# CBB-Proto-r01.net
KiCad netlist of a schematic drawn in EAGLE
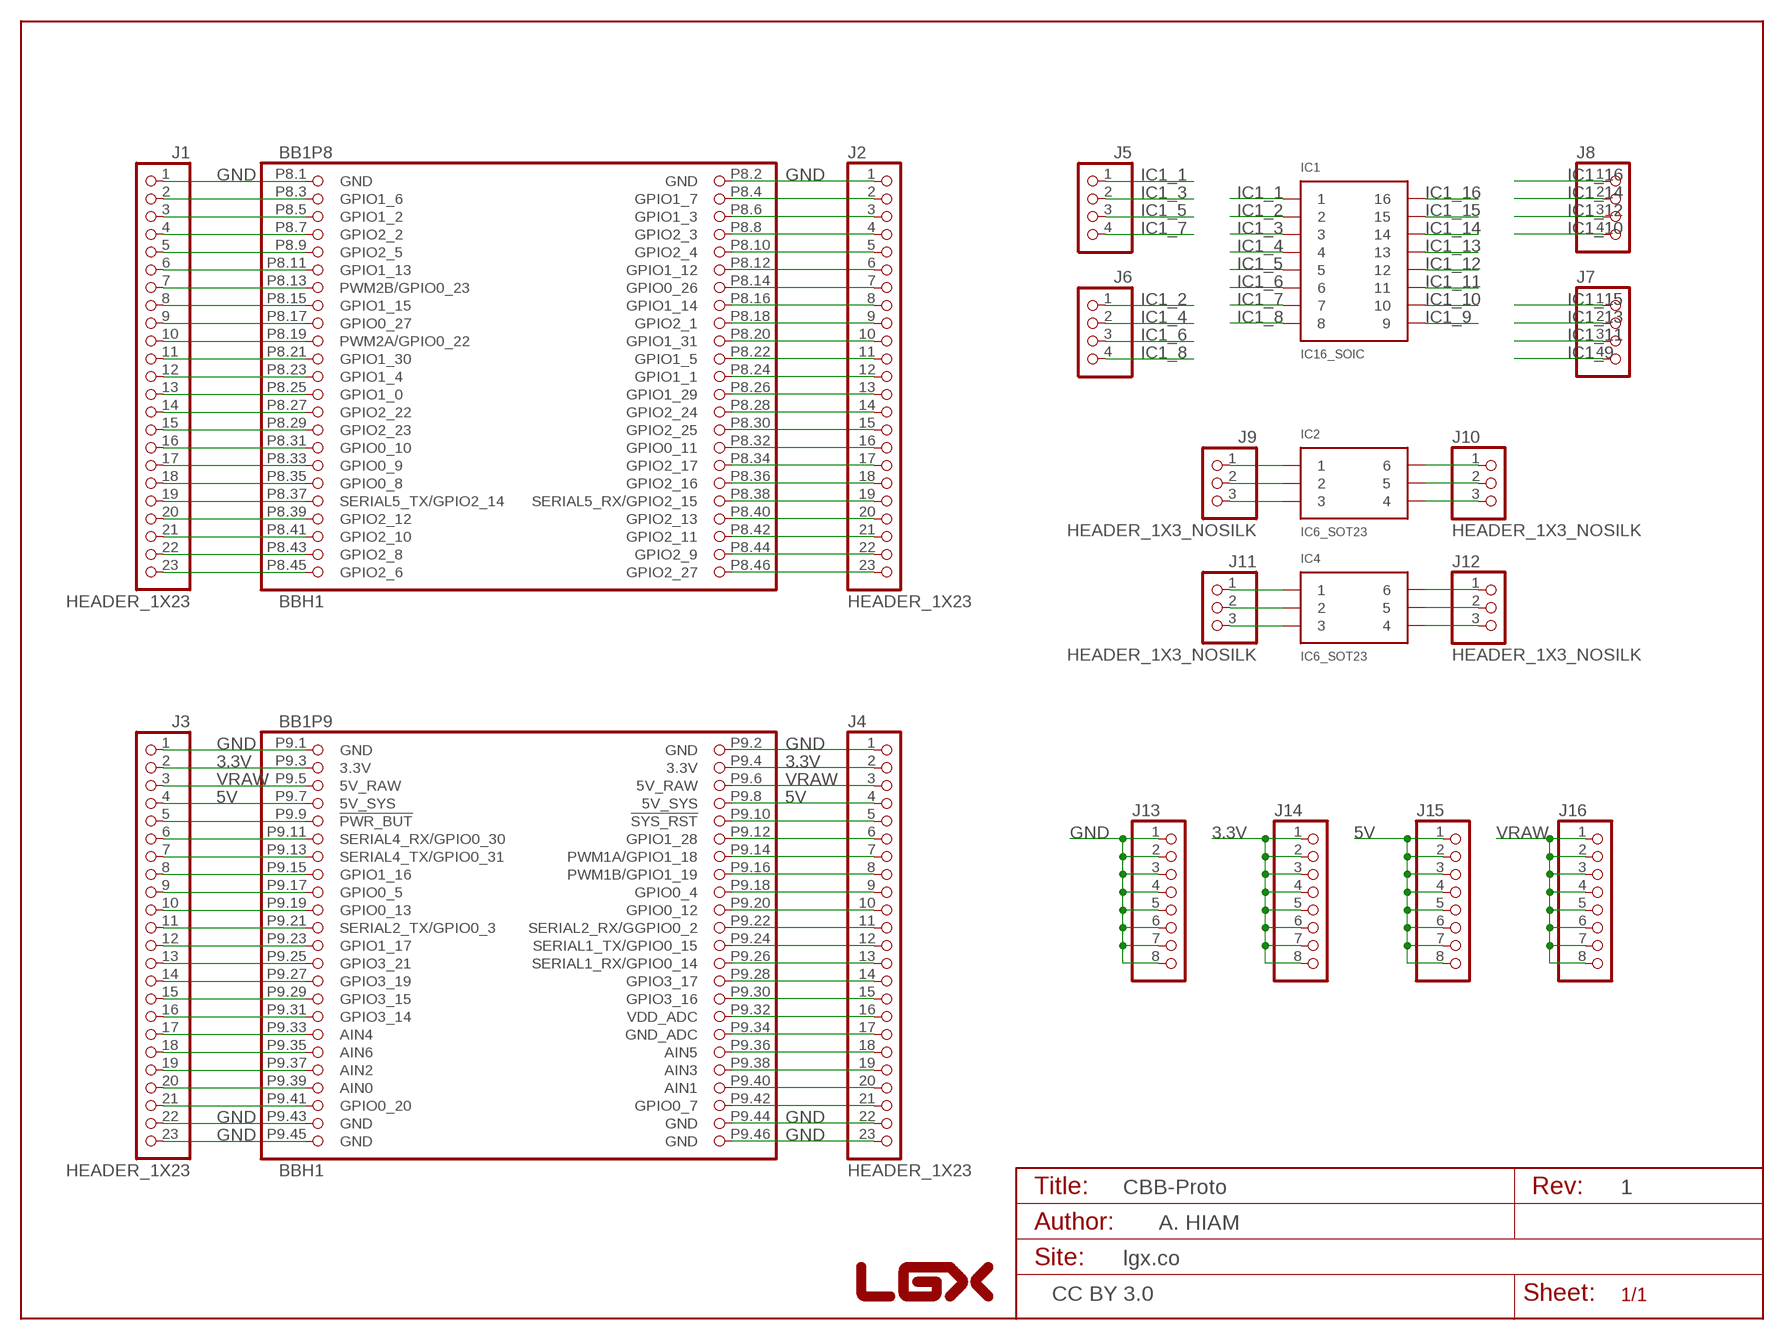
[diagram p0: schematic, sheet 1]

(export (version "E")
  (design (tool "Eeschema 10.0.6"))
  (components
    (comp (ref "BB1")
      (value "BBH1")
      (footprint "eagle-import:BB_CAPE")
      (libsource (lib "eagle-import") (part "BBH1"))
    )
    (comp (ref "IC1")
      (value "IC16_SOIC")
      (footprint "eagle-import:SOIC16")
      (libsource (lib "eagle-import") (part "IC16_SOIC"))
    )
    (comp (ref "IC2")
      (value "IC6_SOT23")
      (footprint "eagle-import:SOT23-6")
      (libsource (lib "eagle-import") (part "IC6_SOT23"))
    )
    (comp (ref "IC4")
      (value "IC6_SOT23")
      (footprint "eagle-import:SOT23-6")
      (libsource (lib "eagle-import") (part "IC6_SOT23"))
    )
    (comp (ref "J1")
      (value "HEADER_1X23")
      (footprint "eagle-import:HEADER_1X23")
      (libsource (lib "eagle-import") (part "HEADER_1X23"))
    )
    (comp (ref "J2")
      (value "HEADER_1X23")
      (footprint "eagle-import:HEADER_1X23")
      (libsource (lib "eagle-import") (part "HEADER_1X23"))
    )
    (comp (ref "J3")
      (value "HEADER_1X23")
      (footprint "eagle-import:HEADER_1X23")
      (libsource (lib "eagle-import") (part "HEADER_1X23"))
    )
    (comp (ref "J4")
      (value "HEADER_1X23")
      (footprint "eagle-import:HEADER_1X23")
      (libsource (lib "eagle-import") (part "HEADER_1X23"))
    )
    (comp (ref "J5")
      (value "HEADER_1X4")
      (footprint "eagle-import:HEADER_1X4")
      (libsource (lib "eagle-import") (part "HEADER_1X4"))
    )
    (comp (ref "J6")
      (value "HEADER_1X4")
      (footprint "eagle-import:HEADER_1X4")
      (libsource (lib "eagle-import") (part "HEADER_1X4"))
    )
    (comp (ref "J7")
      (value "HEADER_1X4")
      (footprint "eagle-import:HEADER_1X4")
      (libsource (lib "eagle-import") (part "HEADER_1X4"))
    )
    (comp (ref "J8")
      (value "HEADER_1X4")
      (footprint "eagle-import:HEADER_1X4")
      (libsource (lib "eagle-import") (part "HEADER_1X4"))
    )
    (comp (ref "J9")
      (value "HEADER_1X3_NOSILK")
      (footprint "eagle-import:HEADER_1X3_NOSILK")
      (libsource (lib "eagle-import") (part "HEADER_1X3_NOSILK"))
    )
    (comp (ref "J10")
      (value "HEADER_1X3_NOSILK")
      (footprint "eagle-import:HEADER_1X3_NOSILK")
      (libsource (lib "eagle-import") (part "HEADER_1X3_NOSILK"))
    )
    (comp (ref "J11")
      (value "HEADER_1X3_NOSILK")
      (footprint "eagle-import:HEADER_1X3_NOSILK")
      (libsource (lib "eagle-import") (part "HEADER_1X3_NOSILK"))
    )
    (comp (ref "J12")
      (value "HEADER_1X3_NOSILK")
      (footprint "eagle-import:HEADER_1X3_NOSILK")
      (libsource (lib "eagle-import") (part "HEADER_1X3_NOSILK"))
    )
    (comp (ref "J13")
      (value "HEADER_1X8")
      (footprint "eagle-import:HEADER_1X8")
      (libsource (lib "eagle-import") (part "HEADER_1X8"))
    )
    (comp (ref "J14")
      (value "HEADER_1X8")
      (footprint "eagle-import:HEADER_1X8")
      (libsource (lib "eagle-import") (part "HEADER_1X8"))
    )
    (comp (ref "J15")
      (value "HEADER_1X8")
      (footprint "eagle-import:HEADER_1X8")
      (libsource (lib "eagle-import") (part "HEADER_1X8"))
    )
    (comp (ref "J16")
      (value "HEADER_1X8")
      (footprint "eagle-import:HEADER_1X8")
      (libsource (lib "eagle-import") (part "HEADER_1X8"))
    )
    (comp (ref "U$1")
      (value "LOGO-LGX")
      (footprint "eagle-import:LOGO-LGX")
      (libsource (lib "eagle-import") (part "LOGO-LGX"))
    )
  )
  (nets
    (net (code "1") (name "/3.3V") (class "Default")
      (node (ref "BB1") (pin "P9.3") (pinfunction "3.3V_P9.3") (pintype "power_in"))
      (node (ref "BB1") (pin "P9.4") (pinfunction "3.3V_P9.4") (pintype "power_in"))
      (node (ref "J14") (pin "1") (pinfunction "1_1") (pintype "passive"))
      (node (ref "J14") (pin "2") (pinfunction "2_2") (pintype "passive"))
      (node (ref "J14") (pin "3") (pinfunction "3_3") (pintype "passive"))
      (node (ref "J14") (pin "4") (pinfunction "4_4") (pintype "passive"))
      (node (ref "J14") (pin "5") (pinfunction "5_5") (pintype "passive"))
      (node (ref "J14") (pin "6") (pinfunction "6_6") (pintype "passive"))
      (node (ref "J14") (pin "7") (pinfunction "7_7") (pintype "passive"))
      (node (ref "J14") (pin "8") (pinfunction "8_8") (pintype "passive"))
      (node (ref "J3") (pin "2") (pinfunction "2_2") (pintype "passive"))
      (node (ref "J4") (pin "2") (pinfunction "2_2") (pintype "passive"))
    )
    (net (code "2") (name "/5V") (class "Default")
      (node (ref "BB1") (pin "P9.7") (pinfunction "5V_SYS_P9.7") (pintype "power_in"))
      (node (ref "BB1") (pin "P9.8") (pinfunction "5V_SYS_P9.8") (pintype "power_in"))
      (node (ref "J15") (pin "1") (pinfunction "1_1") (pintype "passive"))
      (node (ref "J15") (pin "2") (pinfunction "2_2") (pintype "passive"))
      (node (ref "J15") (pin "3") (pinfunction "3_3") (pintype "passive"))
      (node (ref "J15") (pin "4") (pinfunction "4_4") (pintype "passive"))
      (node (ref "J15") (pin "5") (pinfunction "5_5") (pintype "passive"))
      (node (ref "J15") (pin "6") (pinfunction "6_6") (pintype "passive"))
      (node (ref "J15") (pin "7") (pinfunction "7_7") (pintype "passive"))
      (node (ref "J15") (pin "8") (pinfunction "8_8") (pintype "passive"))
      (node (ref "J3") (pin "4") (pinfunction "4_4") (pintype "passive"))
      (node (ref "J4") (pin "4") (pinfunction "4_4") (pintype "passive"))
    )
    (net (code "3") (name "/GND") (class "Default")
      (node (ref "BB1") (pin "P8.1") (pinfunction "GND_P8.1") (pintype "power_in"))
      (node (ref "BB1") (pin "P8.2") (pinfunction "GND_P8.2") (pintype "power_in"))
      (node (ref "BB1") (pin "P9.1") (pinfunction "GND_P9.1") (pintype "power_in"))
      (node (ref "BB1") (pin "P9.2") (pinfunction "GND_P9.2") (pintype "power_in"))
      (node (ref "BB1") (pin "P9.43") (pinfunction "GND_P9.43") (pintype "bidirectional"))
      (node (ref "BB1") (pin "P9.44") (pinfunction "GND_P9.44") (pintype "bidirectional"))
      (node (ref "BB1") (pin "P9.45") (pinfunction "GND_P9.45") (pintype "bidirectional"))
      (node (ref "BB1") (pin "P9.46") (pinfunction "GND_P9.46") (pintype "bidirectional"))
      (node (ref "J1") (pin "1") (pinfunction "1_1") (pintype "passive"))
      (node (ref "J13") (pin "1") (pinfunction "1_1") (pintype "passive"))
      (node (ref "J13") (pin "2") (pinfunction "2_2") (pintype "passive"))
      (node (ref "J13") (pin "3") (pinfunction "3_3") (pintype "passive"))
      (node (ref "J13") (pin "4") (pinfunction "4_4") (pintype "passive"))
      (node (ref "J13") (pin "5") (pinfunction "5_5") (pintype "passive"))
      (node (ref "J13") (pin "6") (pinfunction "6_6") (pintype "passive"))
      (node (ref "J13") (pin "7") (pinfunction "7_7") (pintype "passive"))
      (node (ref "J13") (pin "8") (pinfunction "8_8") (pintype "passive"))
      (node (ref "J2") (pin "1") (pinfunction "1_1") (pintype "passive"))
      (node (ref "J3") (pin "1") (pinfunction "1_1") (pintype "passive"))
      (node (ref "J3") (pin "22") (pinfunction "22_22") (pintype "passive"))
      (node (ref "J3") (pin "23") (pinfunction "23_23") (pintype "passive"))
      (node (ref "J4") (pin "1") (pinfunction "1_1") (pintype "passive"))
      (node (ref "J4") (pin "22") (pinfunction "22_22") (pintype "passive"))
      (node (ref "J4") (pin "23") (pinfunction "23_23") (pintype "passive"))
    )
    (net (code "4") (name "/IC1_1") (class "Default")
      (node (ref "IC1") (pin "1") (pinfunction "1_1") (pintype "bidirectional"))
      (node (ref "J5") (pin "1") (pinfunction "1_1") (pintype "passive"))
    )
    (net (code "5") (name "/IC1_2") (class "Default")
      (node (ref "IC1") (pin "2") (pinfunction "2_2") (pintype "bidirectional"))
      (node (ref "J6") (pin "1") (pinfunction "1_1") (pintype "passive"))
    )
    (net (code "6") (name "/IC1_3") (class "Default")
      (node (ref "IC1") (pin "3") (pinfunction "3_3") (pintype "bidirectional"))
      (node (ref "J5") (pin "2") (pinfunction "2_2") (pintype "passive"))
    )
    (net (code "7") (name "/IC1_4") (class "Default")
      (node (ref "IC1") (pin "4") (pinfunction "4_4") (pintype "bidirectional"))
      (node (ref "J6") (pin "2") (pinfunction "2_2") (pintype "passive"))
    )
    (net (code "8") (name "/IC1_5") (class "Default")
      (node (ref "IC1") (pin "5") (pinfunction "5_5") (pintype "bidirectional"))
      (node (ref "J5") (pin "3") (pinfunction "3_3") (pintype "passive"))
    )
    (net (code "9") (name "/IC1_6") (class "Default")
      (node (ref "IC1") (pin "6") (pinfunction "6_6") (pintype "bidirectional"))
      (node (ref "J6") (pin "3") (pinfunction "3_3") (pintype "passive"))
    )
    (net (code "10") (name "/IC1_7") (class "Default")
      (node (ref "IC1") (pin "7") (pinfunction "7_7") (pintype "bidirectional"))
      (node (ref "J5") (pin "4") (pinfunction "4_4") (pintype "passive"))
    )
    (net (code "11") (name "/IC1_8") (class "Default")
      (node (ref "IC1") (pin "8") (pinfunction "8_8") (pintype "bidirectional"))
      (node (ref "J6") (pin "4") (pinfunction "4_4") (pintype "passive"))
    )
    (net (code "12") (name "/IC1_9") (class "Default")
      (node (ref "IC1") (pin "9") (pinfunction "9_9") (pintype "bidirectional"))
      (node (ref "J7") (pin "4") (pinfunction "4_4") (pintype "passive"))
    )
    (net (code "13") (name "/IC1_10") (class "Default")
      (node (ref "IC1") (pin "10") (pinfunction "10_10") (pintype "bidirectional"))
      (node (ref "J8") (pin "4") (pinfunction "4_4") (pintype "passive"))
    )
    (net (code "14") (name "/IC1_11") (class "Default")
      (node (ref "IC1") (pin "11") (pinfunction "11_11") (pintype "bidirectional"))
      (node (ref "J7") (pin "3") (pinfunction "3_3") (pintype "passive"))
    )
    (net (code "15") (name "/IC1_12") (class "Default")
      (node (ref "IC1") (pin "12") (pinfunction "12_12") (pintype "bidirectional"))
      (node (ref "J8") (pin "3") (pinfunction "3_3") (pintype "passive"))
    )
    (net (code "16") (name "/IC1_13") (class "Default")
      (node (ref "IC1") (pin "13") (pinfunction "13_13") (pintype "bidirectional"))
      (node (ref "J7") (pin "2") (pinfunction "2_2") (pintype "passive"))
    )
    (net (code "17") (name "/IC1_14") (class "Default")
      (node (ref "IC1") (pin "14") (pinfunction "14_14") (pintype "bidirectional"))
      (node (ref "J8") (pin "2") (pinfunction "2_2") (pintype "passive"))
    )
    (net (code "18") (name "/IC1_15") (class "Default")
      (node (ref "IC1") (pin "15") (pinfunction "15_15") (pintype "bidirectional"))
      (node (ref "J7") (pin "1") (pinfunction "1_1") (pintype "passive"))
    )
    (net (code "19") (name "/IC1_16") (class "Default")
      (node (ref "IC1") (pin "16") (pinfunction "16_16") (pintype "bidirectional"))
      (node (ref "J8") (pin "1") (pinfunction "1_1") (pintype "passive"))
    )
    (net (code "20") (name "/VRAW") (class "Default")
      (node (ref "BB1") (pin "P9.5") (pinfunction "5V_RAW_P9.5") (pintype "power_in"))
      (node (ref "BB1") (pin "P9.6") (pinfunction "5V_RAW_P9.6") (pintype "power_in"))
      (node (ref "J16") (pin "1") (pinfunction "1_1") (pintype "passive"))
      (node (ref "J16") (pin "2") (pinfunction "2_2") (pintype "passive"))
      (node (ref "J16") (pin "3") (pinfunction "3_3") (pintype "passive"))
      (node (ref "J16") (pin "4") (pinfunction "4_4") (pintype "passive"))
      (node (ref "J16") (pin "5") (pinfunction "5_5") (pintype "passive"))
      (node (ref "J16") (pin "6") (pinfunction "6_6") (pintype "passive"))
      (node (ref "J16") (pin "7") (pinfunction "7_7") (pintype "passive"))
      (node (ref "J16") (pin "8") (pinfunction "8_8") (pintype "passive"))
      (node (ref "J3") (pin "3") (pinfunction "3_3") (pintype "passive"))
      (node (ref "J4") (pin "3") (pinfunction "3_3") (pintype "passive"))
    )
    (net (code "21") (name "Net-(BB1A-GPIO0_8)") (class "Default")
      (node (ref "BB1") (pin "P8.35") (pinfunction "GPIO0_8_P8.35") (pintype "bidirectional"))
      (node (ref "J1") (pin "18") (pinfunction "18_18") (pintype "passive"))
    )
    (net (code "22") (name "Net-(BB1A-GPIO0_9)") (class "Default")
      (node (ref "BB1") (pin "P8.33") (pinfunction "GPIO0_9_P8.33") (pintype "bidirectional"))
      (node (ref "J1") (pin "17") (pinfunction "17_17") (pintype "passive"))
    )
    (net (code "23") (name "Net-(BB1A-GPIO0_10)") (class "Default")
      (node (ref "BB1") (pin "P8.31") (pinfunction "GPIO0_10_P8.31") (pintype "bidirectional"))
      (node (ref "J1") (pin "16") (pinfunction "16_16") (pintype "passive"))
    )
    (net (code "24") (name "Net-(BB1A-GPIO0_11)") (class "Default")
      (node (ref "BB1") (pin "P8.32") (pinfunction "GPIO0_11_P8.32") (pintype "bidirectional"))
      (node (ref "J2") (pin "16") (pinfunction "16_16") (pintype "passive"))
    )
    (net (code "25") (name "Net-(BB1A-GPIO0_26)") (class "Default")
      (node (ref "BB1") (pin "P8.14") (pinfunction "GPIO0_26_P8.14") (pintype "bidirectional"))
      (node (ref "J2") (pin "7") (pinfunction "7_7") (pintype "passive"))
    )
    (net (code "26") (name "Net-(BB1A-GPIO0_27)") (class "Default")
      (node (ref "BB1") (pin "P8.17") (pinfunction "GPIO0_27_P8.17") (pintype "bidirectional"))
      (node (ref "J1") (pin "9") (pinfunction "9_9") (pintype "passive"))
    )
    (net (code "27") (name "Net-(BB1A-GPIO1_0)") (class "Default")
      (node (ref "BB1") (pin "P8.25") (pinfunction "GPIO1_0_P8.25") (pintype "bidirectional"))
      (node (ref "J1") (pin "13") (pinfunction "13_13") (pintype "passive"))
    )
    (net (code "28") (name "Net-(BB1A-GPIO1_1)") (class "Default")
      (node (ref "BB1") (pin "P8.24") (pinfunction "GPIO1_1_P8.24") (pintype "bidirectional"))
      (node (ref "J2") (pin "12") (pinfunction "12_12") (pintype "passive"))
    )
    (net (code "29") (name "Net-(BB1A-GPIO1_2)") (class "Default")
      (node (ref "BB1") (pin "P8.5") (pinfunction "GPIO1_2_P8.5") (pintype "bidirectional"))
      (node (ref "J1") (pin "3") (pinfunction "3_3") (pintype "passive"))
    )
    (net (code "30") (name "Net-(BB1A-GPIO1_3)") (class "Default")
      (node (ref "BB1") (pin "P8.6") (pinfunction "GPIO1_3_P8.6") (pintype "bidirectional"))
      (node (ref "J2") (pin "3") (pinfunction "3_3") (pintype "passive"))
    )
    (net (code "31") (name "Net-(BB1A-GPIO1_4)") (class "Default")
      (node (ref "BB1") (pin "P8.23") (pinfunction "GPIO1_4_P8.23") (pintype "bidirectional"))
      (node (ref "J1") (pin "12") (pinfunction "12_12") (pintype "passive"))
    )
    (net (code "32") (name "Net-(BB1A-GPIO1_5)") (class "Default")
      (node (ref "BB1") (pin "P8.22") (pinfunction "GPIO1_5_P8.22") (pintype "bidirectional"))
      (node (ref "J2") (pin "11") (pinfunction "11_11") (pintype "passive"))
    )
    (net (code "33") (name "Net-(BB1A-GPIO1_6)") (class "Default")
      (node (ref "BB1") (pin "P8.3") (pinfunction "GPIO1_6_P8.3") (pintype "bidirectional"))
      (node (ref "J1") (pin "2") (pinfunction "2_2") (pintype "passive"))
    )
    (net (code "34") (name "Net-(BB1A-GPIO1_7)") (class "Default")
      (node (ref "BB1") (pin "P8.4") (pinfunction "GPIO1_7_P8.4") (pintype "bidirectional"))
      (node (ref "J2") (pin "2") (pinfunction "2_2") (pintype "passive"))
    )
    (net (code "35") (name "Net-(BB1A-GPIO1_12)") (class "Default")
      (node (ref "BB1") (pin "P8.12") (pinfunction "GPIO1_12_P8.12") (pintype "bidirectional"))
      (node (ref "J2") (pin "6") (pinfunction "6_6") (pintype "passive"))
    )
    (net (code "36") (name "Net-(BB1A-GPIO1_13)") (class "Default")
      (node (ref "BB1") (pin "P8.11") (pinfunction "GPIO1_13_P8.11") (pintype "bidirectional"))
      (node (ref "J1") (pin "6") (pinfunction "6_6") (pintype "passive"))
    )
    (net (code "37") (name "Net-(BB1A-GPIO1_14)") (class "Default")
      (node (ref "BB1") (pin "P8.16") (pinfunction "GPIO1_14_P8.16") (pintype "bidirectional"))
      (node (ref "J2") (pin "8") (pinfunction "8_8") (pintype "passive"))
    )
    (net (code "38") (name "Net-(BB1A-GPIO1_15)") (class "Default")
      (node (ref "BB1") (pin "P8.15") (pinfunction "GPIO1_15_P8.15") (pintype "bidirectional"))
      (node (ref "J1") (pin "8") (pinfunction "8_8") (pintype "passive"))
    )
    (net (code "39") (name "Net-(BB1A-GPIO1_29)") (class "Default")
      (node (ref "BB1") (pin "P8.26") (pinfunction "GPIO1_29_P8.26") (pintype "bidirectional"))
      (node (ref "J2") (pin "13") (pinfunction "13_13") (pintype "passive"))
    )
    (net (code "40") (name "Net-(BB1A-GPIO1_30)") (class "Default")
      (node (ref "BB1") (pin "P8.21") (pinfunction "GPIO1_30_P8.21") (pintype "bidirectional"))
      (node (ref "J1") (pin "11") (pinfunction "11_11") (pintype "passive"))
    )
    (net (code "41") (name "Net-(BB1A-GPIO1_31)") (class "Default")
      (node (ref "BB1") (pin "P8.20") (pinfunction "GPIO1_31_P8.20") (pintype "bidirectional"))
      (node (ref "J2") (pin "10") (pinfunction "10_10") (pintype "passive"))
    )
    (net (code "42") (name "Net-(BB1A-GPIO2_1)") (class "Default")
      (node (ref "BB1") (pin "P8.18") (pinfunction "GPIO2_1_P8.18") (pintype "bidirectional"))
      (node (ref "J2") (pin "9") (pinfunction "9_9") (pintype "passive"))
    )
    (net (code "43") (name "Net-(BB1A-GPIO2_2)") (class "Default")
      (node (ref "BB1") (pin "P8.7") (pinfunction "GPIO2_2_P8.7") (pintype "bidirectional"))
      (node (ref "J1") (pin "4") (pinfunction "4_4") (pintype "passive"))
    )
    (net (code "44") (name "Net-(BB1A-GPIO2_3)") (class "Default")
      (node (ref "BB1") (pin "P8.8") (pinfunction "GPIO2_3_P8.8") (pintype "bidirectional"))
      (node (ref "J2") (pin "4") (pinfunction "4_4") (pintype "passive"))
    )
    (net (code "45") (name "Net-(BB1A-GPIO2_4)") (class "Default")
      (node (ref "BB1") (pin "P8.10") (pinfunction "GPIO2_4_P8.10") (pintype "bidirectional"))
      (node (ref "J2") (pin "5") (pinfunction "5_5") (pintype "passive"))
    )
    (net (code "46") (name "Net-(BB1A-GPIO2_5)") (class "Default")
      (node (ref "BB1") (pin "P8.9") (pinfunction "GPIO2_5_P8.9") (pintype "bidirectional"))
      (node (ref "J1") (pin "5") (pinfunction "5_5") (pintype "passive"))
    )
    (net (code "47") (name "Net-(BB1A-GPIO2_6)") (class "Default")
      (node (ref "BB1") (pin "P8.45") (pinfunction "GPIO2_6_P8.45") (pintype "bidirectional"))
      (node (ref "J1") (pin "23") (pinfunction "23_23") (pintype "passive"))
    )
    (net (code "48") (name "Net-(BB1A-GPIO2_8)") (class "Default")
      (node (ref "BB1") (pin "P8.43") (pinfunction "GPIO2_8_P8.43") (pintype "bidirectional"))
      (node (ref "J1") (pin "22") (pinfunction "22_22") (pintype "passive"))
    )
    (net (code "49") (name "Net-(BB1A-GPIO2_9)") (class "Default")
      (node (ref "BB1") (pin "P8.44") (pinfunction "GPIO2_9_P8.44") (pintype "bidirectional"))
      (node (ref "J2") (pin "22") (pinfunction "22_22") (pintype "passive"))
    )
    (net (code "50") (name "Net-(BB1A-GPIO2_10)") (class "Default")
      (node (ref "BB1") (pin "P8.41") (pinfunction "GPIO2_10_P8.41") (pintype "bidirectional"))
      (node (ref "J1") (pin "21") (pinfunction "21_21") (pintype "passive"))
    )
    (net (code "51") (name "Net-(BB1A-GPIO2_11)") (class "Default")
      (node (ref "BB1") (pin "P8.42") (pinfunction "GPIO2_11_P8.42") (pintype "bidirectional"))
      (node (ref "J2") (pin "21") (pinfunction "21_21") (pintype "passive"))
    )
    (net (code "52") (name "Net-(BB1A-GPIO2_12)") (class "Default")
      (node (ref "BB1") (pin "P8.39") (pinfunction "GPIO2_12_P8.39") (pintype "bidirectional"))
      (node (ref "J1") (pin "20") (pinfunction "20_20") (pintype "passive"))
    )
    (net (code "53") (name "Net-(BB1A-GPIO2_13)") (class "Default")
      (node (ref "BB1") (pin "P8.40") (pinfunction "GPIO2_13_P8.40") (pintype "bidirectional"))
      (node (ref "J2") (pin "20") (pinfunction "20_20") (pintype "passive"))
    )
    (net (code "54") (name "Net-(BB1A-GPIO2_16)") (class "Default")
      (node (ref "BB1") (pin "P8.36") (pinfunction "GPIO2_16_P8.36") (pintype "bidirectional"))
      (node (ref "J2") (pin "18") (pinfunction "18_18") (pintype "passive"))
    )
    (net (code "55") (name "Net-(BB1A-GPIO2_17)") (class "Default")
      (node (ref "BB1") (pin "P8.34") (pinfunction "GPIO2_17_P8.34") (pintype "bidirectional"))
      (node (ref "J2") (pin "17") (pinfunction "17_17") (pintype "passive"))
    )
    (net (code "56") (name "Net-(BB1A-GPIO2_22)") (class "Default")
      (node (ref "BB1") (pin "P8.27") (pinfunction "GPIO2_22_P8.27") (pintype "bidirectional"))
      (node (ref "J1") (pin "14") (pinfunction "14_14") (pintype "passive"))
    )
    (net (code "57") (name "Net-(BB1A-GPIO2_23)") (class "Default")
      (node (ref "BB1") (pin "P8.29") (pinfunction "GPIO2_23_P8.29") (pintype "bidirectional"))
      (node (ref "J1") (pin "15") (pinfunction "15_15") (pintype "passive"))
    )
    (net (code "58") (name "Net-(BB1A-GPIO2_24)") (class "Default")
      (node (ref "BB1") (pin "P8.28") (pinfunction "GPIO2_24_P8.28") (pintype "bidirectional"))
      (node (ref "J2") (pin "14") (pinfunction "14_14") (pintype "passive"))
    )
    (net (code "59") (name "Net-(BB1A-GPIO2_25)") (class "Default")
      (node (ref "BB1") (pin "P8.30") (pinfunction "GPIO2_25_P8.30") (pintype "bidirectional"))
      (node (ref "J2") (pin "15") (pinfunction "15_15") (pintype "passive"))
    )
    (net (code "60") (name "Net-(BB1A-GPIO2_27)") (class "Default")
      (node (ref "BB1") (pin "P8.46") (pinfunction "GPIO2_27_P8.46") (pintype "bidirectional"))
      (node (ref "J2") (pin "23") (pinfunction "23_23") (pintype "passive"))
    )
    (net (code "61") (name "Net-(BB1A-PWM2A{slash}GPIO0_22)") (class "Default")
      (node (ref "BB1") (pin "P8.19") (pinfunction "PWM2A/GPIO0_22_P8.19") (pintype "bidirectional"))
      (node (ref "J1") (pin "10") (pinfunction "10_10") (pintype "passive"))
    )
    (net (code "62") (name "Net-(BB1A-PWM2B{slash}GPIO0_23)") (class "Default")
      (node (ref "BB1") (pin "P8.13") (pinfunction "PWM2B/GPIO0_23_P8.13") (pintype "bidirectional"))
      (node (ref "J1") (pin "7") (pinfunction "7_7") (pintype "passive"))
    )
    (net (code "63") (name "Net-(BB1A-SERIAL5_RX{slash}GPIO2_15)") (class "Default")
      (node (ref "BB1") (pin "P8.38") (pinfunction "SERIAL5_RX/GPIO2_15_P8.38") (pintype "bidirectional"))
      (node (ref "J2") (pin "19") (pinfunction "19_19") (pintype "passive"))
    )
    (net (code "64") (name "Net-(BB1A-SERIAL5_TX{slash}GPIO2_14)") (class "Default")
      (node (ref "BB1") (pin "P8.37") (pinfunction "SERIAL5_TX/GPIO2_14_P8.37") (pintype "bidirectional"))
      (node (ref "J1") (pin "19") (pinfunction "19_19") (pintype "passive"))
    )
    (net (code "65") (name "Net-(BB1B-AIN0)") (class "Default")
      (node (ref "BB1") (pin "P9.39") (pinfunction "AIN0_P9.39") (pintype "input"))
      (node (ref "J3") (pin "20") (pinfunction "20_20") (pintype "passive"))
    )
    (net (code "66") (name "Net-(BB1B-AIN1)") (class "Default")
      (node (ref "BB1") (pin "P9.40") (pinfunction "AIN1_P9.40") (pintype "input"))
      (node (ref "J4") (pin "20") (pinfunction "20_20") (pintype "passive"))
    )
    (net (code "67") (name "Net-(BB1B-AIN2)") (class "Default")
      (node (ref "BB1") (pin "P9.37") (pinfunction "AIN2_P9.37") (pintype "input"))
      (node (ref "J3") (pin "19") (pinfunction "19_19") (pintype "passive"))
    )
    (net (code "68") (name "Net-(BB1B-AIN3)") (class "Default")
      (node (ref "BB1") (pin "P9.38") (pinfunction "AIN3_P9.38") (pintype "input"))
      (node (ref "J4") (pin "19") (pinfunction "19_19") (pintype "passive"))
    )
    (net (code "69") (name "Net-(BB1B-AIN4)") (class "Default")
      (node (ref "BB1") (pin "P9.33") (pinfunction "AIN4_P9.33") (pintype "input"))
      (node (ref "J3") (pin "17") (pinfunction "17_17") (pintype "passive"))
    )
    (net (code "70") (name "Net-(BB1B-AIN5)") (class "Default")
      (node (ref "BB1") (pin "P9.36") (pinfunction "AIN5_P9.36") (pintype "input"))
      (node (ref "J4") (pin "18") (pinfunction "18_18") (pintype "passive"))
    )
    (net (code "71") (name "Net-(BB1B-AIN6)") (class "Default")
      (node (ref "BB1") (pin "P9.35") (pinfunction "AIN6_P9.35") (pintype "input"))
      (node (ref "J3") (pin "18") (pinfunction "18_18") (pintype "passive"))
    )
    (net (code "72") (name "Net-(BB1B-GND_ADC)") (class "Default")
      (node (ref "BB1") (pin "P9.34") (pinfunction "GND_ADC_P9.34") (pintype "bidirectional"))
      (node (ref "J4") (pin "17") (pinfunction "17_17") (pintype "passive"))
    )
    (net (code "73") (name "Net-(BB1B-GPIO0_4)") (class "Default")
      (node (ref "BB1") (pin "P9.18") (pinfunction "GPIO0_4_P9.18") (pintype "bidirectional"))
      (node (ref "J4") (pin "9") (pinfunction "9_9") (pintype "passive"))
    )
    (net (code "74") (name "Net-(BB1B-GPIO0_5)") (class "Default")
      (node (ref "BB1") (pin "P9.17") (pinfunction "GPIO0_5_P9.17") (pintype "bidirectional"))
      (node (ref "J3") (pin "9") (pinfunction "9_9") (pintype "passive"))
    )
    (net (code "75") (name "Net-(BB1B-GPIO0_7)") (class "Default")
      (node (ref "BB1") (pin "P9.42") (pinfunction "GPIO0_7_P9.42") (pintype "bidirectional"))
      (node (ref "J4") (pin "21") (pinfunction "21_21") (pintype "passive"))
    )
    (net (code "76") (name "Net-(BB1B-GPIO0_12)") (class "Default")
      (node (ref "BB1") (pin "P9.20") (pinfunction "GPIO0_12_P9.20") (pintype "bidirectional"))
      (node (ref "J4") (pin "10") (pinfunction "10_10") (pintype "passive"))
    )
    (net (code "77") (name "Net-(BB1B-GPIO0_13)") (class "Default")
      (node (ref "BB1") (pin "P9.19") (pinfunction "GPIO0_13_P9.19") (pintype "bidirectional"))
      (node (ref "J3") (pin "10") (pinfunction "10_10") (pintype "passive"))
    )
    (net (code "78") (name "Net-(BB1B-GPIO0_20)") (class "Default")
      (node (ref "BB1") (pin "P9.41") (pinfunction "GPIO0_20_P9.41") (pintype "bidirectional"))
      (node (ref "J3") (pin "21") (pinfunction "21_21") (pintype "passive"))
    )
    (net (code "79") (name "Net-(BB1B-GPIO1_16)") (class "Default")
      (node (ref "BB1") (pin "P9.15") (pinfunction "GPIO1_16_P9.15") (pintype "bidirectional"))
      (node (ref "J3") (pin "8") (pinfunction "8_8") (pintype "passive"))
    )
    (net (code "80") (name "Net-(BB1B-GPIO1_17)") (class "Default")
      (node (ref "BB1") (pin "P9.23") (pinfunction "GPIO1_17_P9.23") (pintype "bidirectional"))
      (node (ref "J3") (pin "12") (pinfunction "12_12") (pintype "passive"))
    )
    (net (code "81") (name "Net-(BB1B-GPIO1_28)") (class "Default")
      (node (ref "BB1") (pin "P9.12") (pinfunction "GPIO1_28_P9.12") (pintype "bidirectional"))
      (node (ref "J4") (pin "6") (pinfunction "6_6") (pintype "passive"))
    )
    (net (code "82") (name "Net-(BB1B-GPIO3_14)") (class "Default")
      (node (ref "BB1") (pin "P9.31") (pinfunction "GPIO3_14_P9.31") (pintype "bidirectional"))
      (node (ref "J3") (pin "16") (pinfunction "16_16") (pintype "passive"))
    )
    (net (code "83") (name "Net-(BB1B-GPIO3_15)") (class "Default")
      (node (ref "BB1") (pin "P9.29") (pinfunction "GPIO3_15_P9.29") (pintype "bidirectional"))
      (node (ref "J3") (pin "15") (pinfunction "15_15") (pintype "passive"))
    )
    (net (code "84") (name "Net-(BB1B-GPIO3_16)") (class "Default")
      (node (ref "BB1") (pin "P9.30") (pinfunction "GPIO3_16_P9.30") (pintype "bidirectional"))
      (node (ref "J4") (pin "15") (pinfunction "15_15") (pintype "passive"))
    )
    (net (code "85") (name "Net-(BB1B-GPIO3_17)") (class "Default")
      (node (ref "BB1") (pin "P9.28") (pinfunction "GPIO3_17_P9.28") (pintype "bidirectional"))
      (node (ref "J4") (pin "14") (pinfunction "14_14") (pintype "passive"))
    )
    (net (code "86") (name "Net-(BB1B-GPIO3_19)") (class "Default")
      (node (ref "BB1") (pin "P9.27") (pinfunction "GPIO3_19_P9.27") (pintype "bidirectional"))
      (node (ref "J3") (pin "14") (pinfunction "14_14") (pintype "passive"))
    )
    (net (code "87") (name "Net-(BB1B-GPIO3_21)") (class "Default")
      (node (ref "BB1") (pin "P9.25") (pinfunction "GPIO3_21_P9.25") (pintype "bidirectional"))
      (node (ref "J3") (pin "13") (pinfunction "13_13") (pintype "passive"))
    )
    (net (code "88") (name "Net-(BB1B-PWM1A{slash}GPIO1_18)") (class "Default")
      (node (ref "BB1") (pin "P9.14") (pinfunction "PWM1A/GPIO1_18_P9.14") (pintype "bidirectional"))
      (node (ref "J4") (pin "7") (pinfunction "7_7") (pintype "passive"))
    )
    (net (code "89") (name "Net-(BB1B-PWM1B{slash}GPIO1_19)") (class "Default")
      (node (ref "BB1") (pin "P9.16") (pinfunction "PWM1B/GPIO1_19_P9.16") (pintype "bidirectional"))
      (node (ref "J4") (pin "8") (pinfunction "8_8") (pintype "passive"))
    )
    (net (code "90") (name "Net-(BB1B-SERIAL1_RX{slash}GPIO0_14)") (class "Default")
      (node (ref "BB1") (pin "P9.26") (pinfunction "SERIAL1_RX/GPIO0_14_P9.26") (pintype "bidirectional"))
      (node (ref "J4") (pin "13") (pinfunction "13_13") (pintype "passive"))
    )
    (net (code "91") (name "Net-(BB1B-SERIAL1_TX{slash}GPIO0_15)") (class "Default")
      (node (ref "BB1") (pin "P9.24") (pinfunction "SERIAL1_TX/GPIO0_15_P9.24") (pintype "bidirectional"))
      (node (ref "J4") (pin "12") (pinfunction "12_12") (pintype "passive"))
    )
    (net (code "92") (name "Net-(BB1B-SERIAL2_RX{slash}GGPIO0_2)") (class "Default")
      (node (ref "BB1") (pin "P9.22") (pinfunction "SERIAL2_RX/GGPIO0_2_P9.22") (pintype "bidirectional"))
      (node (ref "J4") (pin "11") (pinfunction "11_11") (pintype "passive"))
    )
    (net (code "93") (name "Net-(BB1B-SERIAL2_TX{slash}GPIO0_3)") (class "Default")
      (node (ref "BB1") (pin "P9.21") (pinfunction "SERIAL2_TX/GPIO0_3_P9.21") (pintype "bidirectional"))
      (node (ref "J3") (pin "11") (pinfunction "11_11") (pintype "passive"))
    )
    (net (code "94") (name "Net-(BB1B-SERIAL4_RX{slash}GPIO0_30)") (class "Default")
      (node (ref "BB1") (pin "P9.11") (pinfunction "SERIAL4_RX/GPIO0_30_P9.11") (pintype "bidirectional"))
      (node (ref "J3") (pin "6") (pinfunction "6_6") (pintype "passive"))
    )
    (net (code "95") (name "Net-(BB1B-SERIAL4_TX{slash}GPIO0_31)") (class "Default")
      (node (ref "BB1") (pin "P9.13") (pinfunction "SERIAL4_TX/GPIO0_31_P9.13") (pintype "bidirectional"))
      (node (ref "J3") (pin "7") (pinfunction "7_7") (pintype "passive"))
    )
    (net (code "96") (name "Net-(BB1B-VDD_ADC)") (class "Default")
      (node (ref "BB1") (pin "P9.32") (pinfunction "VDD_ADC_P9.32") (pintype "bidirectional"))
      (node (ref "J4") (pin "16") (pinfunction "16_16") (pintype "passive"))
    )
    (net (code "97") (name "Net-(BB1B-~{PWR_BUT})") (class "Default")
      (node (ref "BB1") (pin "P9.9") (pinfunction "~{PWR_BUT}_P9.9") (pintype "input"))
      (node (ref "J3") (pin "5") (pinfunction "5_5") (pintype "passive"))
    )
    (net (code "98") (name "Net-(BB1B-~{SYS_RST})") (class "Default")
      (node (ref "BB1") (pin "P9.10") (pinfunction "~{SYS_RST}_P9.10") (pintype "input"))
      (node (ref "J4") (pin "5") (pinfunction "5_5") (pintype "passive"))
    )
    (net (code "99") (name "Net-(IC2-Pad1)") (class "Default")
      (node (ref "IC2") (pin "1") (pinfunction "1_1") (pintype "bidirectional"))
      (node (ref "J9") (pin "1") (pinfunction "1_1") (pintype "passive"))
    )
    (net (code "100") (name "Net-(IC2-Pad2)") (class "Default")
      (node (ref "IC2") (pin "2") (pinfunction "2_2") (pintype "bidirectional"))
      (node (ref "J9") (pin "2") (pinfunction "2_2") (pintype "passive"))
    )
    (net (code "101") (name "Net-(IC2-Pad3)") (class "Default")
      (node (ref "IC2") (pin "3") (pinfunction "3_3") (pintype "bidirectional"))
      (node (ref "J9") (pin "3") (pinfunction "3_3") (pintype "passive"))
    )
    (net (code "102") (name "Net-(IC2-Pad4)") (class "Default")
      (node (ref "IC2") (pin "4") (pinfunction "4_4") (pintype "bidirectional"))
      (node (ref "J10") (pin "3") (pinfunction "3_3") (pintype "passive"))
    )
    (net (code "103") (name "Net-(IC2-Pad5)") (class "Default")
      (node (ref "IC2") (pin "5") (pinfunction "5_5") (pintype "bidirectional"))
      (node (ref "J10") (pin "2") (pinfunction "2_2") (pintype "passive"))
    )
    (net (code "104") (name "Net-(IC2-Pad6)") (class "Default")
      (node (ref "IC2") (pin "6") (pinfunction "6_6") (pintype "bidirectional"))
      (node (ref "J10") (pin "1") (pinfunction "1_1") (pintype "passive"))
    )
    (net (code "105") (name "Net-(IC4-Pad1)") (class "Default")
      (node (ref "IC4") (pin "1") (pinfunction "1_1") (pintype "bidirectional"))
      (node (ref "J11") (pin "1") (pinfunction "1_1") (pintype "passive"))
    )
    (net (code "106") (name "Net-(IC4-Pad2)") (class "Default")
      (node (ref "IC4") (pin "2") (pinfunction "2_2") (pintype "bidirectional"))
      (node (ref "J11") (pin "2") (pinfunction "2_2") (pintype "passive"))
    )
    (net (code "107") (name "Net-(IC4-Pad3)") (class "Default")
      (node (ref "IC4") (pin "3") (pinfunction "3_3") (pintype "bidirectional"))
      (node (ref "J11") (pin "3") (pinfunction "3_3") (pintype "passive"))
    )
    (net (code "108") (name "Net-(IC4-Pad4)") (class "Default")
      (node (ref "IC4") (pin "4") (pinfunction "4_4") (pintype "bidirectional"))
      (node (ref "J12") (pin "3") (pinfunction "3_3") (pintype "passive"))
    )
    (net (code "109") (name "Net-(IC4-Pad5)") (class "Default")
      (node (ref "IC4") (pin "5") (pinfunction "5_5") (pintype "bidirectional"))
      (node (ref "J12") (pin "2") (pinfunction "2_2") (pintype "passive"))
    )
    (net (code "110") (name "Net-(IC4-Pad6)") (class "Default")
      (node (ref "IC4") (pin "6") (pinfunction "6_6") (pintype "bidirectional"))
      (node (ref "J12") (pin "1") (pinfunction "1_1") (pintype "passive"))
    )
  )
)
